# SCH_Wavu_2025-10-24.net
KiCad netlist of a schematic drawn in EasyEDA
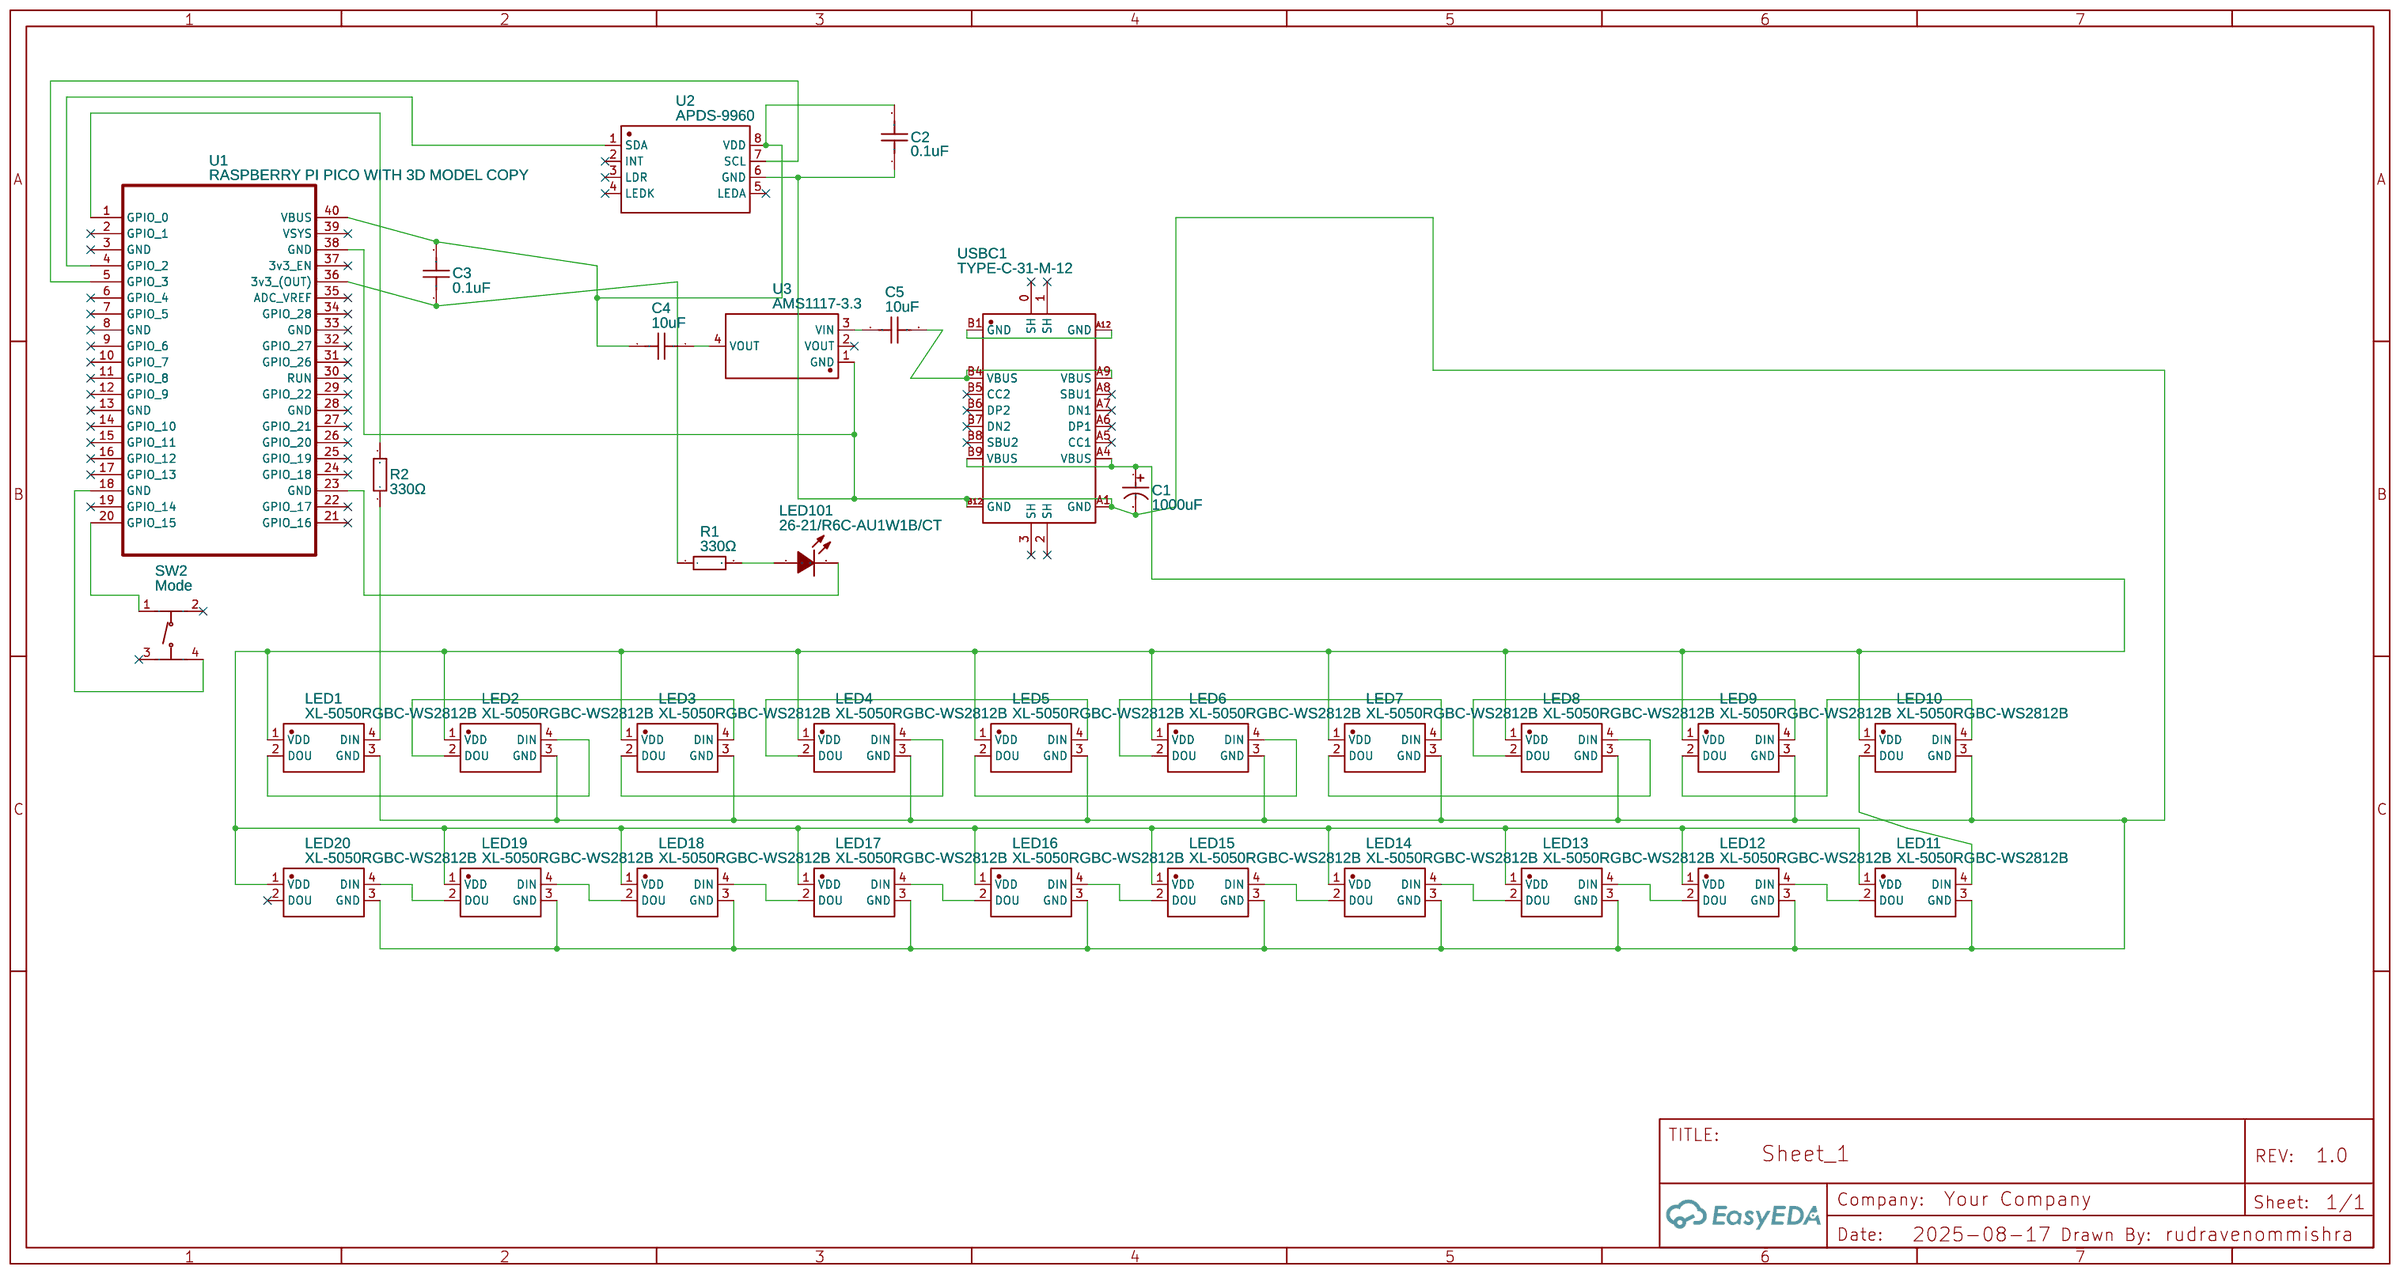
[diagram p0: schematic sheet]

(export (version "E")
  (design (tool "Eeschema 10.0.6"))
  (components
    (comp (ref "C1")
      (value "1000uF")
      (fields
        (field (name "Manufacturer Part") "GR108M010G15RR0VL4FP0")
        (field (name "Manufacturer") "CX(承兴)")
      )
      (libsource (lib "") (part "1000uF 10V 10*15"))
    )
    (comp (ref "C2")
      (value "0.1uF")
      (fields
        (field (name "Manufacturer Part") "CC0805KRX7R9BB104")
        (field (name "Manufacturer") "YAGEO(国巨)")
      )
      (libsource (lib "") (part "CC0805KRX7R9BB104"))
    )
    (comp (ref "C3")
      (value "0.1uF")
      (fields
        (field (name "Manufacturer Part") "CC0805KRX7R9BB104")
        (field (name "Manufacturer") "YAGEO(国巨)")
      )
      (libsource (lib "") (part "CC0805KRX7R9BB104"))
    )
    (comp (ref "C4")
      (value "10uF")
      (fields
        (field (name "Manufacturer Part") "V106K0805X5R250NHP")
        (field (name "Manufacturer") "VIIYONG(微容)")
      )
      (libsource (lib "") (part "V106K0805X5R250NHP"))
    )
    (comp (ref "C5")
      (value "10uF")
      (fields
        (field (name "Manufacturer Part") "V106K0805X5R250NHP")
        (field (name "Manufacturer") "VIIYONG(微容)")
      )
      (libsource (lib "") (part "V106K0805X5R250NHP"))
    )
    (comp (ref "LED1")
      (value "XL-5050RGBC-WS2812B")
      (fields (field (name "Manufacturer") "XINGLIGHT(成兴光)"))
      (libsource (lib "") (part "XL-5050RGBC-WS2812B"))
    )
    (comp (ref "LED2")
      (value "XL-5050RGBC-WS2812B")
      (fields (field (name "Manufacturer") "XINGLIGHT(成兴光)"))
      (libsource (lib "") (part "XL-5050RGBC-WS2812B"))
    )
    (comp (ref "LED3")
      (value "XL-5050RGBC-WS2812B")
      (fields (field (name "Manufacturer") "XINGLIGHT(成兴光)"))
      (libsource (lib "") (part "XL-5050RGBC-WS2812B"))
    )
    (comp (ref "LED4")
      (value "XL-5050RGBC-WS2812B")
      (fields (field (name "Manufacturer") "XINGLIGHT(成兴光)"))
      (libsource (lib "") (part "XL-5050RGBC-WS2812B"))
    )
    (comp (ref "LED5")
      (value "XL-5050RGBC-WS2812B")
      (fields (field (name "Manufacturer") "XINGLIGHT(成兴光)"))
      (libsource (lib "") (part "XL-5050RGBC-WS2812B"))
    )
    (comp (ref "LED6")
      (value "XL-5050RGBC-WS2812B")
      (fields (field (name "Manufacturer") "XINGLIGHT(成兴光)"))
      (libsource (lib "") (part "XL-5050RGBC-WS2812B"))
    )
    (comp (ref "LED7")
      (value "XL-5050RGBC-WS2812B")
      (fields (field (name "Manufacturer") "XINGLIGHT(成兴光)"))
      (libsource (lib "") (part "XL-5050RGBC-WS2812B"))
    )
    (comp (ref "LED8")
      (value "XL-5050RGBC-WS2812B")
      (fields (field (name "Manufacturer") "XINGLIGHT(成兴光)"))
      (libsource (lib "") (part "XL-5050RGBC-WS2812B"))
    )
    (comp (ref "LED9")
      (value "XL-5050RGBC-WS2812B")
      (fields (field (name "Manufacturer") "XINGLIGHT(成兴光)"))
      (libsource (lib "") (part "XL-5050RGBC-WS2812B"))
    )
    (comp (ref "LED10")
      (value "XL-5050RGBC-WS2812B")
      (fields (field (name "Manufacturer") "XINGLIGHT(成兴光)"))
      (libsource (lib "") (part "XL-5050RGBC-WS2812B"))
    )
    (comp (ref "LED11")
      (value "XL-5050RGBC-WS2812B")
      (fields (field (name "Manufacturer") "XINGLIGHT(成兴光)"))
      (libsource (lib "") (part "XL-5050RGBC-WS2812B"))
    )
    (comp (ref "LED12")
      (value "XL-5050RGBC-WS2812B")
      (fields (field (name "Manufacturer") "XINGLIGHT(成兴光)"))
      (libsource (lib "") (part "XL-5050RGBC-WS2812B"))
    )
    (comp (ref "LED13")
      (value "XL-5050RGBC-WS2812B")
      (fields (field (name "Manufacturer") "XINGLIGHT(成兴光)"))
      (libsource (lib "") (part "XL-5050RGBC-WS2812B"))
    )
    (comp (ref "LED14")
      (value "XL-5050RGBC-WS2812B")
      (fields (field (name "Manufacturer") "XINGLIGHT(成兴光)"))
      (libsource (lib "") (part "XL-5050RGBC-WS2812B"))
    )
    (comp (ref "LED15")
      (value "XL-5050RGBC-WS2812B")
      (fields (field (name "Manufacturer") "XINGLIGHT(成兴光)"))
      (libsource (lib "") (part "XL-5050RGBC-WS2812B"))
    )
    (comp (ref "LED16")
      (value "XL-5050RGBC-WS2812B")
      (fields (field (name "Manufacturer") "XINGLIGHT(成兴光)"))
      (libsource (lib "") (part "XL-5050RGBC-WS2812B"))
    )
    (comp (ref "LED17")
      (value "XL-5050RGBC-WS2812B")
      (fields (field (name "Manufacturer") "XINGLIGHT(成兴光)"))
      (libsource (lib "") (part "XL-5050RGBC-WS2812B"))
    )
    (comp (ref "LED18")
      (value "XL-5050RGBC-WS2812B")
      (fields (field (name "Manufacturer") "XINGLIGHT(成兴光)"))
      (libsource (lib "") (part "XL-5050RGBC-WS2812B"))
    )
    (comp (ref "LED19")
      (value "XL-5050RGBC-WS2812B")
      (fields (field (name "Manufacturer") "XINGLIGHT(成兴光)"))
      (libsource (lib "") (part "XL-5050RGBC-WS2812B"))
    )
    (comp (ref "LED20")
      (value "XL-5050RGBC-WS2812B")
      (fields (field (name "Manufacturer") "XINGLIGHT(成兴光)"))
      (libsource (lib "") (part "XL-5050RGBC-WS2812B"))
    )
    (comp (ref "LED101")
      (value "26-21/R6C-AU1W1B/CT")
      (fields (field (name "Manufacturer") "EVERLIGHT(亿光)"))
      (libsource (lib "") (part "26-21/R6C-AU1W1B/CT"))
    )
    (comp (ref "R1")
      (value "330Ω")
      (fields
        (field (name "Manufacturer Part") "0805W8F3300T5E")
        (field (name "Manufacturer") "UNI-ROYAL(厚声)")
      )
      (libsource (lib "") (part "0805W8F3300T5E"))
    )
    (comp (ref "R2")
      (value "330Ω")
      (fields
        (field (name "Manufacturer Part") "0805W8F3300T5E")
        (field (name "Manufacturer") "UNI-ROYAL(厚声)")
      )
      (libsource (lib "") (part "0805W8F3300T5E_1"))
    )
    (comp (ref "SW2")
      (value "Mode")
      (fields
        (field (name "Manufacturer Part") "TS-1187A-B-A-B")
        (field (name "Manufacturer") "XKB Connectivity(中国星坤)")
      )
      (libsource (lib "") (part "TS-1187A-B-A-B"))
    )
    (comp (ref "U1")
      (value "RASPBERRY PI PICO WITH 3D MODEL COPY")
      (libsource (lib "") (part "RASPBERRY PI PICO WITH 3D MODEL COPY"))
    )
    (comp (ref "U2")
      (value "APDS-9960")
      (fields (field (name "Manufacturer") "Broadcom(博通)"))
      (libsource (lib "") (part "APDS-9960"))
    )
    (comp (ref "U3")
      (value "AMS1117-3.3")
      (fields (field (name "Manufacturer") "AMS"))
      (libsource (lib "") (part "AMS1117-3.3"))
    )
    (comp (ref "USBC1")
      (value "TYPE-C-31-M-12")
      (fields (field (name "Manufacturer") "韩国韩荣"))
      (libsource (lib "") (part "TYPE-C-31-M-12"))
    )
  )
  (nets
    (net (code "1") (name "Net-(C4-Pad2)") (class "Default")
      (node (ref "C4") (pin "2") (pinfunction "2_2") (pintype "unspecified"))
      (node (ref "U3") (pin "4") (pinfunction "VOUT_4") (pintype "unspecified"))
    )
    (net (code "2") (name "Net-(C5-Pad2)") (class "Default")
      (node (ref "C5") (pin "2") (pinfunction "2_2") (pintype "unspecified"))
      (node (ref "USBC1") (pin "A9") (pinfunction "VBUS_A9") (pintype "unspecified"))
      (node (ref "USBC1") (pin "B4") (pinfunction "VBUS_B4") (pintype "unspecified"))
    )
    (net (code "3") (name "Net-(LED1-DIN)") (class "Default")
      (node (ref "LED1") (pin "4") (pinfunction "DIN_4") (pintype "unspecified"))
      (node (ref "R2") (pin "1") (pinfunction "1_1") (pintype "input"))
    )
    (net (code "4") (name "Net-(LED1-DOU)") (class "Default")
      (node (ref "LED1") (pin "2") (pinfunction "DOU_2") (pintype "unspecified"))
      (node (ref "LED2") (pin "4") (pinfunction "DIN_4") (pintype "unspecified"))
    )
    (net (code "5") (name "Net-(LED1-GND)") (class "Default")
      (node (ref "C1") (pin "2") (pinfunction "2_2") (pintype "input"))
      (node (ref "C2") (pin "1") (pinfunction "1_1") (pintype "unspecified"))
      (node (ref "LED1") (pin "3") (pinfunction "GND_3") (pintype "unspecified"))
      (node (ref "LED10") (pin "3") (pinfunction "GND_3") (pintype "unspecified"))
      (node (ref "LED11") (pin "3") (pinfunction "GND_3") (pintype "unspecified"))
      (node (ref "LED12") (pin "3") (pinfunction "GND_3") (pintype "unspecified"))
      (node (ref "LED13") (pin "3") (pinfunction "GND_3") (pintype "unspecified"))
      (node (ref "LED14") (pin "3") (pinfunction "GND_3") (pintype "unspecified"))
      (node (ref "LED15") (pin "3") (pinfunction "GND_3") (pintype "unspecified"))
      (node (ref "LED16") (pin "3") (pinfunction "GND_3") (pintype "unspecified"))
      (node (ref "LED17") (pin "3") (pinfunction "GND_3") (pintype "unspecified"))
      (node (ref "LED18") (pin "3") (pinfunction "GND_3") (pintype "unspecified"))
      (node (ref "LED19") (pin "3") (pinfunction "GND_3") (pintype "unspecified"))
      (node (ref "LED2") (pin "3") (pinfunction "GND_3") (pintype "unspecified"))
      (node (ref "LED20") (pin "3") (pinfunction "GND_3") (pintype "unspecified"))
      (node (ref "LED3") (pin "3") (pinfunction "GND_3") (pintype "unspecified"))
      (node (ref "LED4") (pin "3") (pinfunction "GND_3") (pintype "unspecified"))
      (node (ref "LED5") (pin "3") (pinfunction "GND_3") (pintype "unspecified"))
      (node (ref "LED6") (pin "3") (pinfunction "GND_3") (pintype "unspecified"))
      (node (ref "LED7") (pin "3") (pinfunction "GND_3") (pintype "unspecified"))
      (node (ref "LED8") (pin "3") (pinfunction "GND_3") (pintype "unspecified"))
      (node (ref "LED9") (pin "3") (pinfunction "GND_3") (pintype "unspecified"))
      (node (ref "U1") (pin "38") (pinfunction "GND_38") (pintype "unspecified"))
      (node (ref "U2") (pin "6") (pinfunction "GND_6") (pintype "unspecified"))
      (node (ref "U3") (pin "1") (pinfunction "GND_1") (pintype "unspecified"))
      (node (ref "USBC1") (pin "A1") (pinfunction "GND_A1") (pintype "unspecified"))
      (node (ref "USBC1") (pin "B12") (pinfunction "GND_B12") (pintype "unspecified"))
    )
    (net (code "6") (name "Net-(LED1-VDD)") (class "Default")
      (node (ref "C1") (pin "1") (pinfunction "1_1") (pintype "input"))
      (node (ref "LED1") (pin "1") (pinfunction "VDD_1") (pintype "unspecified"))
      (node (ref "LED10") (pin "1") (pinfunction "VDD_1") (pintype "unspecified"))
      (node (ref "LED11") (pin "1") (pinfunction "VDD_1") (pintype "unspecified"))
      (node (ref "LED12") (pin "1") (pinfunction "VDD_1") (pintype "unspecified"))
      (node (ref "LED13") (pin "1") (pinfunction "VDD_1") (pintype "unspecified"))
      (node (ref "LED14") (pin "1") (pinfunction "VDD_1") (pintype "unspecified"))
      (node (ref "LED15") (pin "1") (pinfunction "VDD_1") (pintype "unspecified"))
      (node (ref "LED16") (pin "1") (pinfunction "VDD_1") (pintype "unspecified"))
      (node (ref "LED17") (pin "1") (pinfunction "VDD_1") (pintype "unspecified"))
      (node (ref "LED18") (pin "1") (pinfunction "VDD_1") (pintype "unspecified"))
      (node (ref "LED19") (pin "1") (pinfunction "VDD_1") (pintype "unspecified"))
      (node (ref "LED2") (pin "1") (pinfunction "VDD_1") (pintype "unspecified"))
      (node (ref "LED20") (pin "1") (pinfunction "VDD_1") (pintype "unspecified"))
      (node (ref "LED3") (pin "1") (pinfunction "VDD_1") (pintype "unspecified"))
      (node (ref "LED4") (pin "1") (pinfunction "VDD_1") (pintype "unspecified"))
      (node (ref "LED5") (pin "1") (pinfunction "VDD_1") (pintype "unspecified"))
      (node (ref "LED6") (pin "1") (pinfunction "VDD_1") (pintype "unspecified"))
      (node (ref "LED7") (pin "1") (pinfunction "VDD_1") (pintype "unspecified"))
      (node (ref "LED8") (pin "1") (pinfunction "VDD_1") (pintype "unspecified"))
      (node (ref "LED9") (pin "1") (pinfunction "VDD_1") (pintype "unspecified"))
      (node (ref "USBC1") (pin "A4") (pinfunction "VBUS_A4") (pintype "unspecified"))
      (node (ref "USBC1") (pin "B9") (pinfunction "VBUS_B9") (pintype "unspecified"))
    )
    (net (code "7") (name "Net-(LED2-DOU)") (class "Default")
      (node (ref "LED2") (pin "2") (pinfunction "DOU_2") (pintype "unspecified"))
      (node (ref "LED3") (pin "4") (pinfunction "DIN_4") (pintype "unspecified"))
    )
    (net (code "8") (name "Net-(LED3-DOU)") (class "Default")
      (node (ref "LED3") (pin "2") (pinfunction "DOU_2") (pintype "unspecified"))
      (node (ref "LED4") (pin "4") (pinfunction "DIN_4") (pintype "unspecified"))
    )
    (net (code "9") (name "Net-(LED4-DOU)") (class "Default")
      (node (ref "LED4") (pin "2") (pinfunction "DOU_2") (pintype "unspecified"))
      (node (ref "LED5") (pin "4") (pinfunction "DIN_4") (pintype "unspecified"))
    )
    (net (code "10") (name "Net-(LED5-DOU)") (class "Default")
      (node (ref "LED5") (pin "2") (pinfunction "DOU_2") (pintype "unspecified"))
      (node (ref "LED6") (pin "4") (pinfunction "DIN_4") (pintype "unspecified"))
    )
    (net (code "11") (name "Net-(LED6-DOU)") (class "Default")
      (node (ref "LED6") (pin "2") (pinfunction "DOU_2") (pintype "unspecified"))
      (node (ref "LED7") (pin "4") (pinfunction "DIN_4") (pintype "unspecified"))
    )
    (net (code "12") (name "Net-(LED7-DOU)") (class "Default")
      (node (ref "LED7") (pin "2") (pinfunction "DOU_2") (pintype "unspecified"))
      (node (ref "LED8") (pin "4") (pinfunction "DIN_4") (pintype "unspecified"))
    )
    (net (code "13") (name "Net-(LED8-DOU)") (class "Default")
      (node (ref "LED8") (pin "2") (pinfunction "DOU_2") (pintype "unspecified"))
      (node (ref "LED9") (pin "4") (pinfunction "DIN_4") (pintype "unspecified"))
    )
    (net (code "14") (name "Net-(LED10-DIN)") (class "Default")
      (node (ref "LED10") (pin "4") (pinfunction "DIN_4") (pintype "unspecified"))
      (node (ref "LED9") (pin "2") (pinfunction "DOU_2") (pintype "unspecified"))
    )
    (net (code "15") (name "Net-(LED10-DOU)") (class "Default")
      (node (ref "LED10") (pin "2") (pinfunction "DOU_2") (pintype "unspecified"))
      (node (ref "LED11") (pin "4") (pinfunction "DIN_4") (pintype "unspecified"))
    )
    (net (code "16") (name "Net-(LED11-DOU)") (class "Default")
      (node (ref "LED11") (pin "2") (pinfunction "DOU_2") (pintype "unspecified"))
      (node (ref "LED12") (pin "4") (pinfunction "DIN_4") (pintype "unspecified"))
    )
    (net (code "17") (name "Net-(LED12-DOU)") (class "Default")
      (node (ref "LED12") (pin "2") (pinfunction "DOU_2") (pintype "unspecified"))
      (node (ref "LED13") (pin "4") (pinfunction "DIN_4") (pintype "unspecified"))
    )
    (net (code "18") (name "Net-(LED13-DOU)") (class "Default")
      (node (ref "LED13") (pin "2") (pinfunction "DOU_2") (pintype "unspecified"))
      (node (ref "LED14") (pin "4") (pinfunction "DIN_4") (pintype "unspecified"))
    )
    (net (code "19") (name "Net-(LED14-DOU)") (class "Default")
      (node (ref "LED14") (pin "2") (pinfunction "DOU_2") (pintype "unspecified"))
      (node (ref "LED15") (pin "4") (pinfunction "DIN_4") (pintype "unspecified"))
    )
    (net (code "20") (name "Net-(LED15-DOU)") (class "Default")
      (node (ref "LED15") (pin "2") (pinfunction "DOU_2") (pintype "unspecified"))
      (node (ref "LED16") (pin "4") (pinfunction "DIN_4") (pintype "unspecified"))
    )
    (net (code "21") (name "Net-(LED16-DOU)") (class "Default")
      (node (ref "LED16") (pin "2") (pinfunction "DOU_2") (pintype "unspecified"))
      (node (ref "LED17") (pin "4") (pinfunction "DIN_4") (pintype "unspecified"))
    )
    (net (code "22") (name "Net-(LED17-DOU)") (class "Default")
      (node (ref "LED17") (pin "2") (pinfunction "DOU_2") (pintype "unspecified"))
      (node (ref "LED18") (pin "4") (pinfunction "DIN_4") (pintype "unspecified"))
    )
    (net (code "23") (name "Net-(LED18-DOU)") (class "Default")
      (node (ref "LED18") (pin "2") (pinfunction "DOU_2") (pintype "unspecified"))
      (node (ref "LED19") (pin "4") (pinfunction "DIN_4") (pintype "unspecified"))
    )
    (net (code "24") (name "Net-(LED19-DOU)") (class "Default")
      (node (ref "LED19") (pin "2") (pinfunction "DOU_2") (pintype "unspecified"))
      (node (ref "LED20") (pin "4") (pinfunction "DIN_4") (pintype "unspecified"))
    )
    (net (code "25") (name "Net-(LED101-A)") (class "Default")
      (node (ref "LED101") (pin "1") (pinfunction "A_1") (pintype "unspecified"))
      (node (ref "R1") (pin "2") (pinfunction "2_2") (pintype "input"))
    )
    (net (code "26") (name "Net-(LED101-K)") (class "Default")
      (node (ref "LED101") (pin "2") (pinfunction "K_2") (pintype "unspecified"))
      (node (ref "U1") (pin "23") (pinfunction "GND_23") (pintype "unspecified"))
    )
    (net (code "27") (name "Net-(SW2-A)") (class "Default")
      (node (ref "SW2") (pin "1") (pinfunction "A_1") (pintype "unspecified"))
      (node (ref "U1") (pin "20") (pinfunction "GPIO_15_20") (pintype "unspecified"))
    )
    (net (code "28") (name "Net-(SW2-D)") (class "Default")
      (node (ref "SW2") (pin "4") (pinfunction "D_4") (pintype "unspecified"))
      (node (ref "U1") (pin "18") (pinfunction "GND_18") (pintype "unspecified"))
    )
    (net (code "29") (name "Net-(U1-3v3_(OUT))") (class "Default")
      (node (ref "C3") (pin "1") (pinfunction "1_1") (pintype "unspecified"))
      (node (ref "R1") (pin "1") (pinfunction "1_1") (pintype "input"))
      (node (ref "U1") (pin "36") (pinfunction "3v3_(OUT)_36") (pintype "unspecified"))
    )
    (net (code "30") (name "Net-(U1-GPIO_0)") (class "Default")
      (node (ref "R2") (pin "2") (pinfunction "2_2") (pintype "input"))
      (node (ref "U1") (pin "1") (pinfunction "GPIO_0_1") (pintype "unspecified"))
    )
    (net (code "31") (name "Net-(U1-GPIO_2)") (class "Default")
      (node (ref "U1") (pin "4") (pinfunction "GPIO_2_4") (pintype "unspecified"))
      (node (ref "U2") (pin "1") (pinfunction "SDA_1") (pintype "unspecified"))
    )
    (net (code "32") (name "Net-(U1-GPIO_3)") (class "Default")
      (node (ref "U1") (pin "5") (pinfunction "GPIO_3_5") (pintype "unspecified"))
      (node (ref "U2") (pin "7") (pinfunction "SCL_7") (pintype "unspecified"))
    )
    (net (code "33") (name "Net-(U1-VBUS)") (class "Default")
      (node (ref "C2") (pin "2") (pinfunction "2_2") (pintype "unspecified"))
      (node (ref "C3") (pin "2") (pinfunction "2_2") (pintype "unspecified"))
      (node (ref "C4") (pin "1") (pinfunction "1_1") (pintype "unspecified"))
      (node (ref "U1") (pin "40") (pinfunction "VBUS_40") (pintype "unspecified"))
      (node (ref "U2") (pin "8") (pinfunction "VDD_8") (pintype "unspecified"))
    )
    (net (code "34") (name "Net-(U3-VIN)") (class "Default")
      (node (ref "C5") (pin "1") (pinfunction "1_1") (pintype "unspecified"))
      (node (ref "U3") (pin "3") (pinfunction "VIN_3") (pintype "unspecified"))
    )
    (net (code "35") (name "Net-(USBC1-GND-PadA12)") (class "Default")
      (node (ref "USBC1") (pin "A12") (pinfunction "GND_A12") (pintype "unspecified"))
      (node (ref "USBC1") (pin "B1") (pinfunction "GND_B1") (pintype "unspecified"))
    )
    (net (code "36") (name "unconnected-(LED20-DOU-Pad2)") (class "Default")
      (node (ref "LED20") (pin "2") (pinfunction "DOU_2") (pintype "unspecified+no_connect"))
    )
    (net (code "37") (name "unconnected-(SW2-B-Pad2)") (class "Default")
      (node (ref "SW2") (pin "2") (pinfunction "B_2") (pintype "unspecified+no_connect"))
    )
    (net (code "38") (name "unconnected-(SW2-C-Pad3)") (class "Default")
      (node (ref "SW2") (pin "3") (pinfunction "C_3") (pintype "unspecified+no_connect"))
    )
    (net (code "39") (name "unconnected-(U1-3v3_EN-Pad37)") (class "Default")
      (node (ref "U1") (pin "37") (pinfunction "3v3_EN_37") (pintype "unspecified+no_connect"))
    )
    (net (code "40") (name "unconnected-(U1-ADC_VREF-Pad35)") (class "Default")
      (node (ref "U1") (pin "35") (pinfunction "ADC_VREF_35") (pintype "unspecified+no_connect"))
    )
    (net (code "41") (name "unconnected-(U1-GND-Pad3)") (class "Default")
      (node (ref "U1") (pin "3") (pinfunction "GND_3") (pintype "unspecified+no_connect"))
    )
    (net (code "42") (name "unconnected-(U1-GND-Pad8)") (class "Default")
      (node (ref "U1") (pin "8") (pinfunction "GND_8") (pintype "unspecified+no_connect"))
    )
    (net (code "43") (name "unconnected-(U1-GND-Pad13)") (class "Default")
      (node (ref "U1") (pin "13") (pinfunction "GND_13") (pintype "unspecified+no_connect"))
    )
    (net (code "44") (name "unconnected-(U1-GND-Pad28)") (class "Default")
      (node (ref "U1") (pin "28") (pinfunction "GND_28") (pintype "unspecified+no_connect"))
    )
    (net (code "45") (name "unconnected-(U1-GND-Pad33)") (class "Default")
      (node (ref "U1") (pin "33") (pinfunction "GND_33") (pintype "unspecified+no_connect"))
    )
    (net (code "46") (name "unconnected-(U1-GPIO_1-Pad2)") (class "Default")
      (node (ref "U1") (pin "2") (pinfunction "GPIO_1_2") (pintype "unspecified+no_connect"))
    )
    (net (code "47") (name "unconnected-(U1-GPIO_4-Pad6)") (class "Default")
      (node (ref "U1") (pin "6") (pinfunction "GPIO_4_6") (pintype "unspecified+no_connect"))
    )
    (net (code "48") (name "unconnected-(U1-GPIO_5-Pad7)") (class "Default")
      (node (ref "U1") (pin "7") (pinfunction "GPIO_5_7") (pintype "unspecified+no_connect"))
    )
    (net (code "49") (name "unconnected-(U1-GPIO_6-Pad9)") (class "Default")
      (node (ref "U1") (pin "9") (pinfunction "GPIO_6_9") (pintype "unspecified+no_connect"))
    )
    (net (code "50") (name "unconnected-(U1-GPIO_7-Pad10)") (class "Default")
      (node (ref "U1") (pin "10") (pinfunction "GPIO_7_10") (pintype "unspecified+no_connect"))
    )
    (net (code "51") (name "unconnected-(U1-GPIO_8-Pad11)") (class "Default")
      (node (ref "U1") (pin "11") (pinfunction "GPIO_8_11") (pintype "unspecified+no_connect"))
    )
    (net (code "52") (name "unconnected-(U1-GPIO_9-Pad12)") (class "Default")
      (node (ref "U1") (pin "12") (pinfunction "GPIO_9_12") (pintype "unspecified+no_connect"))
    )
    (net (code "53") (name "unconnected-(U1-GPIO_10-Pad14)") (class "Default")
      (node (ref "U1") (pin "14") (pinfunction "GPIO_10_14") (pintype "unspecified+no_connect"))
    )
    (net (code "54") (name "unconnected-(U1-GPIO_11-Pad15)") (class "Default")
      (node (ref "U1") (pin "15") (pinfunction "GPIO_11_15") (pintype "unspecified+no_connect"))
    )
    (net (code "55") (name "unconnected-(U1-GPIO_12-Pad16)") (class "Default")
      (node (ref "U1") (pin "16") (pinfunction "GPIO_12_16") (pintype "unspecified+no_connect"))
    )
    (net (code "56") (name "unconnected-(U1-GPIO_13-Pad17)") (class "Default")
      (node (ref "U1") (pin "17") (pinfunction "GPIO_13_17") (pintype "unspecified+no_connect"))
    )
    (net (code "57") (name "unconnected-(U1-GPIO_14-Pad19)") (class "Default")
      (node (ref "U1") (pin "19") (pinfunction "GPIO_14_19") (pintype "unspecified+no_connect"))
    )
    (net (code "58") (name "unconnected-(U1-GPIO_16-Pad21)") (class "Default")
      (node (ref "U1") (pin "21") (pinfunction "GPIO_16_21") (pintype "unspecified+no_connect"))
    )
    (net (code "59") (name "unconnected-(U1-GPIO_17-Pad22)") (class "Default")
      (node (ref "U1") (pin "22") (pinfunction "GPIO_17_22") (pintype "unspecified+no_connect"))
    )
    (net (code "60") (name "unconnected-(U1-GPIO_18-Pad24)") (class "Default")
      (node (ref "U1") (pin "24") (pinfunction "GPIO_18_24") (pintype "unspecified+no_connect"))
    )
    (net (code "61") (name "unconnected-(U1-GPIO_19-Pad25)") (class "Default")
      (node (ref "U1") (pin "25") (pinfunction "GPIO_19_25") (pintype "unspecified+no_connect"))
    )
    (net (code "62") (name "unconnected-(U1-GPIO_20-Pad26)") (class "Default")
      (node (ref "U1") (pin "26") (pinfunction "GPIO_20_26") (pintype "unspecified+no_connect"))
    )
    (net (code "63") (name "unconnected-(U1-GPIO_21-Pad27)") (class "Default")
      (node (ref "U1") (pin "27") (pinfunction "GPIO_21_27") (pintype "unspecified+no_connect"))
    )
    (net (code "64") (name "unconnected-(U1-GPIO_22-Pad29)") (class "Default")
      (node (ref "U1") (pin "29") (pinfunction "GPIO_22_29") (pintype "unspecified+no_connect"))
    )
    (net (code "65") (name "unconnected-(U1-GPIO_26-Pad31)") (class "Default")
      (node (ref "U1") (pin "31") (pinfunction "GPIO_26_31") (pintype "unspecified+no_connect"))
    )
    (net (code "66") (name "unconnected-(U1-GPIO_27-Pad32)") (class "Default")
      (node (ref "U1") (pin "32") (pinfunction "GPIO_27_32") (pintype "unspecified+no_connect"))
    )
    (net (code "67") (name "unconnected-(U1-GPIO_28-Pad34)") (class "Default")
      (node (ref "U1") (pin "34") (pinfunction "GPIO_28_34") (pintype "unspecified+no_connect"))
    )
    (net (code "68") (name "unconnected-(U1-RUN-Pad30)") (class "Default")
      (node (ref "U1") (pin "30") (pinfunction "RUN_30") (pintype "unspecified+no_connect"))
    )
    (net (code "69") (name "unconnected-(U1-VSYS-Pad39)") (class "Default")
      (node (ref "U1") (pin "39") (pinfunction "VSYS_39") (pintype "unspecified+no_connect"))
    )
    (net (code "70") (name "unconnected-(U2-INT-Pad2)") (class "Default")
      (node (ref "U2") (pin "2") (pinfunction "INT_2") (pintype "unspecified+no_connect"))
    )
    (net (code "71") (name "unconnected-(U2-LDR-Pad3)") (class "Default")
      (node (ref "U2") (pin "3") (pinfunction "LDR_3") (pintype "unspecified+no_connect"))
    )
    (net (code "72") (name "unconnected-(U2-LEDA-Pad5)") (class "Default")
      (node (ref "U2") (pin "5") (pinfunction "LEDA_5") (pintype "unspecified+no_connect"))
    )
    (net (code "73") (name "unconnected-(U2-LEDK-Pad4)") (class "Default")
      (node (ref "U2") (pin "4") (pinfunction "LEDK_4") (pintype "unspecified+no_connect"))
    )
    (net (code "74") (name "unconnected-(U3-VOUT-Pad2)") (class "Default")
      (node (ref "U3") (pin "2") (pinfunction "VOUT_2") (pintype "unspecified+no_connect"))
    )
    (net (code "75") (name "unconnected-(USBC1-CC1-PadA5)") (class "Default")
      (node (ref "USBC1") (pin "A5") (pinfunction "CC1_A5") (pintype "unspecified+no_connect"))
    )
    (net (code "76") (name "unconnected-(USBC1-CC2-PadB5)") (class "Default")
      (node (ref "USBC1") (pin "B5") (pinfunction "CC2_B5") (pintype "unspecified+no_connect"))
    )
    (net (code "77") (name "unconnected-(USBC1-DN1-PadA7)") (class "Default")
      (node (ref "USBC1") (pin "A7") (pinfunction "DN1_A7") (pintype "unspecified+no_connect"))
    )
    (net (code "78") (name "unconnected-(USBC1-DN2-PadB7)") (class "Default")
      (node (ref "USBC1") (pin "B7") (pinfunction "DN2_B7") (pintype "unspecified+no_connect"))
    )
    (net (code "79") (name "unconnected-(USBC1-DP1-PadA6)") (class "Default")
      (node (ref "USBC1") (pin "A6") (pinfunction "DP1_A6") (pintype "unspecified+no_connect"))
    )
    (net (code "80") (name "unconnected-(USBC1-DP2-PadB6)") (class "Default")
      (node (ref "USBC1") (pin "B6") (pinfunction "DP2_B6") (pintype "unspecified+no_connect"))
    )
    (net (code "81") (name "unconnected-(USBC1-SBU1-PadA8)") (class "Default")
      (node (ref "USBC1") (pin "A8") (pinfunction "SBU1_A8") (pintype "unspecified+no_connect"))
    )
    (net (code "82") (name "unconnected-(USBC1-SBU2-PadB8)") (class "Default")
      (node (ref "USBC1") (pin "B8") (pinfunction "SBU2_B8") (pintype "unspecified+no_connect"))
    )
    (net (code "83") (name "unconnected-(USBC1-SH-Pad0)") (class "Default")
      (node (ref "USBC1") (pin "0") (pinfunction "SH_0") (pintype "unspecified+no_connect"))
    )
    (net (code "84") (name "unconnected-(USBC1-SH-Pad1)") (class "Default")
      (node (ref "USBC1") (pin "1") (pinfunction "SH_1") (pintype "unspecified+no_connect"))
    )
    (net (code "85") (name "unconnected-(USBC1-SH-Pad2)") (class "Default")
      (node (ref "USBC1") (pin "2") (pinfunction "SH_2") (pintype "unspecified+no_connect"))
    )
    (net (code "86") (name "unconnected-(USBC1-SH-Pad3)") (class "Default")
      (node (ref "USBC1") (pin "3") (pinfunction "SH_3") (pintype "unspecified+no_connect"))
    )
  )
)
